# untitled.net
KiCad netlist of a schematic drawn in EAGLE
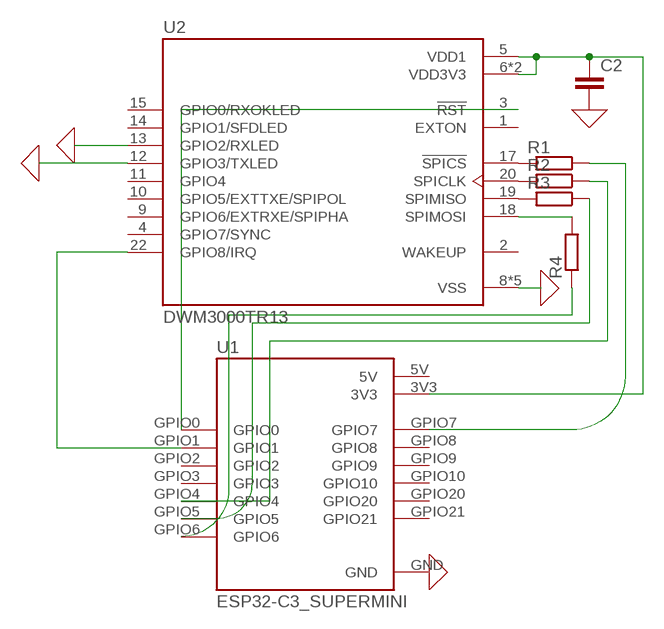
[diagram p0: schematic, sheet 1]

(export (version "E")
  (design (tool "Eeschema 10.0.6"))
  (components
    (comp (ref "C2")
      (value "C-EUC0402K")
      (footprint "eagle-import:C0402K")
      (libsource (lib "eagle-import") (part "C-EUC0402K"))
    )
    (comp (ref "R1")
      (value "SMK")
      (footprint "eagle-import:SMK")
      (libsource (lib "eagle-import") (part "SMK"))
    )
    (comp (ref "R2")
      (value "SMK")
      (footprint "eagle-import:SMK")
      (libsource (lib "eagle-import") (part "SMK"))
    )
    (comp (ref "R3")
      (value "SMK")
      (footprint "eagle-import:SMK")
      (libsource (lib "eagle-import") (part "SMK"))
    )
    (comp (ref "R4")
      (value "SMK")
      (footprint "eagle-import:SMK")
      (libsource (lib "eagle-import") (part "SMK"))
    )
    (comp (ref "U1")
      (value "ESP32-C3_SUPERMINI")
      (footprint "eagle-import:MODULE_ESP32-C3_SUPERMINI")
      (fields (field (name "MF") "Espressif Systems") (field (name "MP") "ESP32-C3 SuperMini"))
      (libsource (lib "eagle-import") (part "ESP32-C3_SUPERMINI"))
    )
    (comp (ref "U2")
      (value "DWM3000TR13")
      (footprint "eagle-import:XCVR_DWM3000TR13")
      (fields (field (name "MF") "Qorvo"))
      (libsource (lib "eagle-import") (part "DWM3000TR13"))
    )
  )
  (nets
    (net (code "1") (name "/5V") (class "Default")
      (node (ref "U1") (pin "5V") (pinfunction "5V_5V") (pintype "power_in"))
    )
    (net (code "2") (name "GND") (class "Default")
      (node (ref "C2") (pin "2") (pinfunction "2_2") (pintype "passive"))
      (node (ref "U1") (pin "GND") (pinfunction "GND_GND") (pintype "power_in"))
      (node (ref "U2") (pin "12") (pinfunction "GPIO3/TXLED_12") (pintype "bidirectional"))
      (node (ref "U2") (pin "13") (pinfunction "GPIO2/RXLED_13") (pintype "bidirectional"))
      (node (ref "U2") (pin "16") (pinfunction "VSS_16") (pintype "power_in"))
      (node (ref "U2") (pin "21") (pinfunction "VSS_21") (pintype "power_in"))
      (node (ref "U2") (pin "23") (pinfunction "VSS_23") (pintype "power_in"))
      (node (ref "U2") (pin "24") (pinfunction "VSS_24") (pintype "power_in"))
      (node (ref "U2") (pin "8") (pinfunction "VSS_8") (pintype "power_in"))
    )
    (net (code "3") (name "Net-(R1-Pad1)") (class "Default")
      (node (ref "R1") (pin "1") (pinfunction "1_1") (pintype "passive"))
      (node (ref "U1") (pin "GPIO7") (pinfunction "GPIO7_GPIO7") (pintype "bidirectional"))
    )
    (net (code "4") (name "Net-(R2-Pad1)") (class "Default")
      (node (ref "R2") (pin "1") (pinfunction "1_1") (pintype "passive"))
      (node (ref "U1") (pin "GPIO4") (pinfunction "GPIO4_GPIO4") (pintype "bidirectional"))
    )
    (net (code "5") (name "Net-(R3-Pad1)") (class "Default")
      (node (ref "R3") (pin "1") (pinfunction "1_1") (pintype "passive"))
      (node (ref "U1") (pin "GPIO5") (pinfunction "GPIO5_GPIO5") (pintype "bidirectional"))
    )
    (net (code "6") (name "Net-(R4-Pad2)") (class "Default")
      (node (ref "R4") (pin "2") (pinfunction "2_2") (pintype "passive"))
      (node (ref "U1") (pin "GPIO6") (pinfunction "GPIO6_GPIO6") (pintype "bidirectional"))
    )
    (net (code "7") (name "Net-(U2-GPIO8{slash}IRQ)") (class "Default")
      (node (ref "U1") (pin "GPIO1") (pinfunction "GPIO1_GPIO1") (pintype "bidirectional"))
      (node (ref "U2") (pin "22") (pinfunction "GPIO8/IRQ_22") (pintype "bidirectional"))
    )
    (net (code "8") (name "Net-(U2-SPICLK)") (class "Default")
      (node (ref "R2") (pin "2") (pinfunction "2_2") (pintype "passive"))
      (node (ref "U2") (pin "20") (pinfunction "SPICLK_20") (pintype "input"))
    )
    (net (code "9") (name "Net-(U2-SPIMISO)") (class "Default")
      (node (ref "R3") (pin "2") (pinfunction "2_2") (pintype "passive"))
      (node (ref "U2") (pin "19") (pinfunction "SPIMISO_19") (pintype "output"))
    )
    (net (code "10") (name "Net-(U2-SPIMOSI)") (class "Default")
      (node (ref "R4") (pin "1") (pinfunction "1_1") (pintype "passive"))
      (node (ref "U2") (pin "18") (pinfunction "SPIMOSI_18") (pintype "input"))
    )
    (net (code "11") (name "Net-(U2-VDD1)") (class "Default")
      (node (ref "C2") (pin "1") (pinfunction "1_1") (pintype "passive"))
      (node (ref "U1") (pin "3V3") (pinfunction "3V3_3V3") (pintype "power_in"))
      (node (ref "U2") (pin "5") (pinfunction "VDD1_5") (pintype "power_in"))
      (node (ref "U2") (pin "6") (pinfunction "VDD3V3_6") (pintype "power_in"))
      (node (ref "U2") (pin "7") (pinfunction "VDD3V3_7") (pintype "power_in"))
    )
    (net (code "12") (name "Net-(U2-~{RST})") (class "Default")
      (node (ref "U1") (pin "GPIO0") (pinfunction "GPIO0_GPIO0") (pintype "bidirectional"))
      (node (ref "U2") (pin "3") (pinfunction "~{RST}_3") (pintype "output"))
    )
    (net (code "13") (name "Net-(U2-~{SPICS})") (class "Default")
      (node (ref "R1") (pin "2") (pinfunction "2_2") (pintype "passive"))
      (node (ref "U2") (pin "17") (pinfunction "~{SPICS}_17") (pintype "input"))
    )
    (net (code "14") (name "unconnected-(U1-PadGPIO2)") (class "Default")
      (node (ref "U1") (pin "GPIO2") (pinfunction "GPIO2_GPIO2") (pintype "bidirectional"))
    )
    (net (code "15") (name "unconnected-(U1-PadGPIO3)") (class "Default")
      (node (ref "U1") (pin "GPIO3") (pinfunction "GPIO3_GPIO3") (pintype "bidirectional"))
    )
    (net (code "16") (name "unconnected-(U1-PadGPIO8)") (class "Default")
      (node (ref "U1") (pin "GPIO8") (pinfunction "GPIO8_GPIO8") (pintype "bidirectional"))
    )
    (net (code "17") (name "unconnected-(U1-PadGPIO9)") (class "Default")
      (node (ref "U1") (pin "GPIO9") (pinfunction "GPIO9_GPIO9") (pintype "bidirectional"))
    )
    (net (code "18") (name "unconnected-(U1-PadGPIO10)") (class "Default")
      (node (ref "U1") (pin "GPIO10") (pinfunction "GPIO10_GPIO10") (pintype "bidirectional"))
    )
    (net (code "19") (name "unconnected-(U1-PadGPIO20)") (class "Default")
      (node (ref "U1") (pin "GPIO20") (pinfunction "GPIO20_GPIO20") (pintype "bidirectional"))
    )
    (net (code "20") (name "unconnected-(U1-PadGPIO21)") (class "Default")
      (node (ref "U1") (pin "GPIO21") (pinfunction "GPIO21_GPIO21") (pintype "bidirectional"))
    )
    (net (code "21") (name "unconnected-(U2-EXTON-Pad1)") (class "Default")
      (node (ref "U2") (pin "1") (pinfunction "EXTON_1") (pintype "output"))
    )
    (net (code "22") (name "unconnected-(U2-GPIO0{slash}RXOKLED-Pad15)") (class "Default")
      (node (ref "U2") (pin "15") (pinfunction "GPIO0/RXOKLED_15") (pintype "bidirectional"))
    )
    (net (code "23") (name "unconnected-(U2-GPIO1{slash}SFDLED-Pad14)") (class "Default")
      (node (ref "U2") (pin "14") (pinfunction "GPIO1/SFDLED_14") (pintype "bidirectional"))
    )
    (net (code "24") (name "unconnected-(U2-GPIO4-Pad11)") (class "Default")
      (node (ref "U2") (pin "11") (pinfunction "GPIO4_11") (pintype "bidirectional"))
    )
    (net (code "25") (name "unconnected-(U2-GPIO5{slash}EXTTXE{slash}SPIPOL-Pad10)") (class "Default")
      (node (ref "U2") (pin "10") (pinfunction "GPIO5/EXTTXE/SPIPOL_10") (pintype "bidirectional"))
    )
    (net (code "26") (name "unconnected-(U2-GPIO6{slash}EXTRXE{slash}SPIPHA-Pad9)") (class "Default")
      (node (ref "U2") (pin "9") (pinfunction "GPIO6/EXTRXE/SPIPHA_9") (pintype "bidirectional"))
    )
    (net (code "27") (name "unconnected-(U2-GPIO7{slash}SYNC-Pad4)") (class "Default")
      (node (ref "U2") (pin "4") (pinfunction "GPIO7/SYNC_4") (pintype "bidirectional"))
    )
    (net (code "28") (name "unconnected-(U2-WAKEUP-Pad2)") (class "Default")
      (node (ref "U2") (pin "2") (pinfunction "WAKEUP_2") (pintype "bidirectional"))
    )
  )
)
